# CH32X035F7P6-R0.net
KiCad netlist of a schematic drawn in Altium Designer
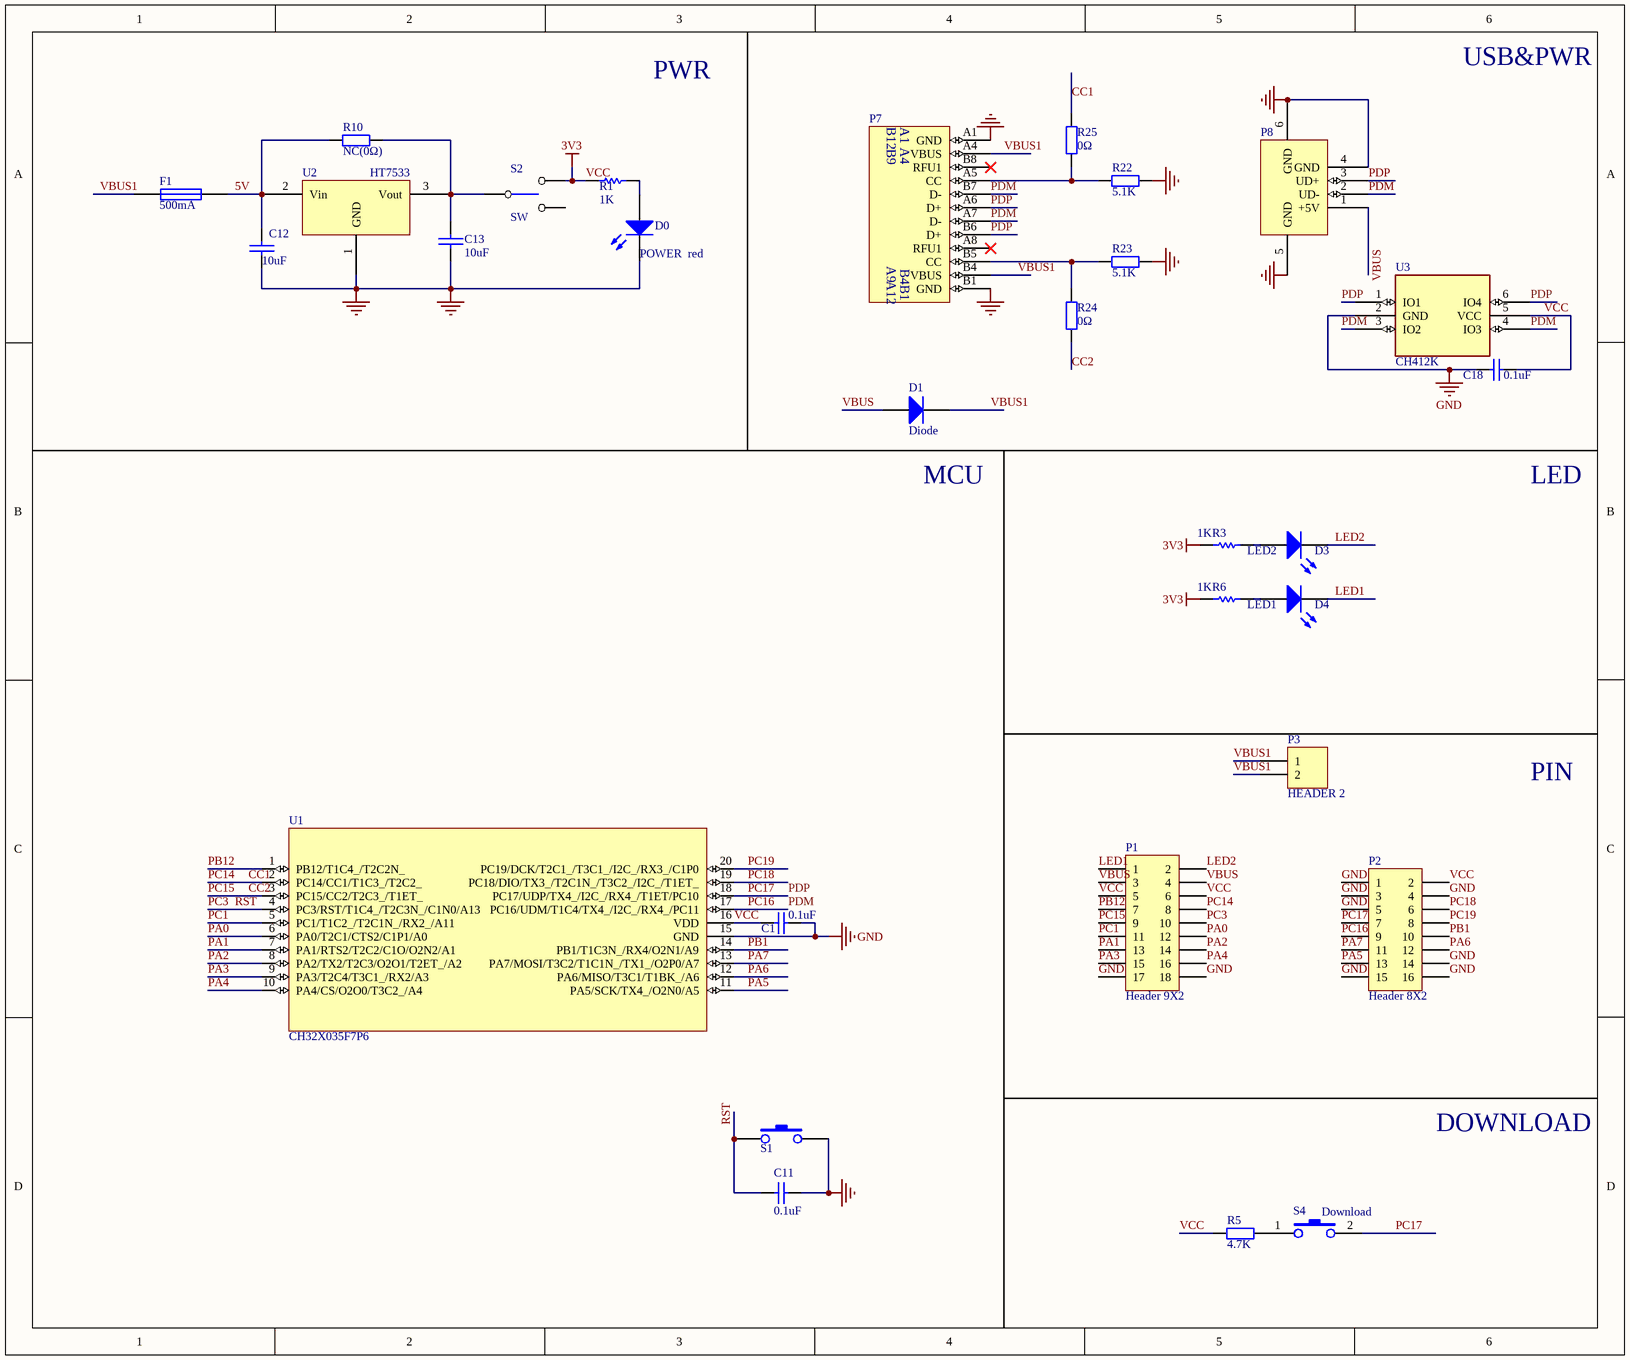
[diagram p0: CH32X035F7P6-R0.SchDoc]

(export (version "E")
  (design (tool "Eeschema 10.0.6"))
  (components
    (comp (ref "C1")
      (value "0.1uF")
      (footprint "0603_C")
      (description "Capacitor")
      (libsource (lib "Miscellaneous Devices") (part "Cap"))
    )
    (comp (ref "C11")
      (value "0.1uF")
      (footprint "0603_C")
      (description "Capacitor")
      (fields (field (name "PUBLISHER") "Altium Limited"))
      (libsource (lib "*") (part "Cap"))
    )
    (comp (ref "C12")
      (value "10uF")
      (footprint "0603_C")
      (description "Capacitor")
      (libsource (lib "*") (part "CAP"))
    )
    (comp (ref "C13")
      (value "10uF")
      (footprint "0603_C")
      (description "Capacitor")
      (libsource (lib "*") (part "CAP"))
    )
    (comp (ref "C18")
      (value "0.1uF")
      (footprint "0603_C")
      (description "Capacitor")
      (libsource (lib "Miscellaneous Devices") (part "Cap"))
    )
    (comp (ref "D0")
      (value "POWER  red")
      (footprint "0603+")
      (description "Typical INFRARED GaAs LED")
      (fields (field (name "PUBLISHER") "Altium Limited"))
      (libsource (lib "*") (part "LED0"))
    )
    (comp (ref "D1")
      (value "Diode")
      (footprint "SOD-123")
      (description "Default Diode")
      (fields (field (name "PUBLISHER") "Altium Limited"))
      (libsource (lib "Miscellaneous Devices") (part "Diode"))
    )
    (comp (ref "D3")
      (value "LED2")
      (footprint "0603+")
      (description "Typical INFRARED GaAs LED")
      (fields (field (name "PUBLISHER") "Altium Limited"))
      (libsource (lib "*") (part "LED0"))
    )
    (comp (ref "D4")
      (value "LED1")
      (footprint "0603+")
      (description "Typical INFRARED GaAs LED")
      (fields (field (name "PUBLISHER") "Altium Limited"))
      (libsource (lib "*") (part "LED0"))
    )
    (comp (ref "F1")
      (value "500mA")
      (footprint "0603")
      (description "Fuse")
      (libsource (lib "*") (part "FUSE1"))
    )
    (comp (ref "P1")
      (value "Header 9X2")
      (footprint "IDC18-2.54mm")
      (description "Header, 9-Pin, Dual row")
      (fields (field (name "PUBLISHER") "Altium Limited"))
      (libsource (lib "Miscellaneous Connectors") (part "Header 9X2"))
    )
    (comp (ref "P2")
      (value "Header 8X2")
      (footprint "IDC16-2.54mm")
      (description "Header, 8-Pin, Dual row")
      (fields (field (name "PUBLISHER") "Altium Limited"))
      (libsource (lib "Miscellaneous Connectors") (part "Header 8X2"))
    )
    (comp (ref "P3")
      (value "HEADER 2")
      (footprint "SIP2-2.54mm")
      (description "Header, 2-Pin")
      (libsource (lib "wch_sch_others") (part "HEADER 2"))
    )
    (comp (ref "P7")
      (value "TYPE-C")
      (footprint "TYPE-C-Receptacle-2.0")
      (libsource (lib "*") (part "TYPE-C1"))
    )
    (comp (ref "P8")
      (value "USB_A")
      (footprint "USBAF")
      (description "USB Port")
      (libsource (lib "*") (part "USB"))
    )
    (comp (ref "R1")
      (value "1K")
      (footprint "0603")
      (description "Semiconductor Resistor")
      (libsource (lib "*") (part "Res Semi"))
    )
    (comp (ref "R3")
      (value "1K")
      (footprint "0603")
      (description "Semiconductor Resistor")
      (libsource (lib "*") (part "Res Semi"))
    )
    (comp (ref "R5")
      (value "4.7K")
      (footprint "0603")
      (description "Resistor")
      (libsource (lib "") (part "Res2_1"))
    )
    (comp (ref "R6")
      (value "1K")
      (footprint "0603")
      (description "Semiconductor Resistor")
      (libsource (lib "*") (part "Res Semi"))
    )
    (comp (ref "R10")
      (value "NC(0Ω)")
      (footprint "0603")
      (description "Resistor")
      (libsource (lib "*") (part "Res2"))
    )
    (comp (ref "R22")
      (value "5.1K")
      (footprint "0603")
      (description "Resistor")
      (libsource (lib "") (part "Res2_1"))
    )
    (comp (ref "R23")
      (value "5.1K")
      (footprint "0603")
      (description "Resistor")
      (libsource (lib "") (part "Res2_1"))
    )
    (comp (ref "R24")
      (value "0Ω")
      (footprint "0603")
      (description "Resistor")
      (libsource (lib "Miscellaneous Devices") (part "Res2"))
    )
    (comp (ref "R25")
      (value "0Ω")
      (footprint "0603")
      (description "Resistor")
      (libsource (lib "Miscellaneous Devices") (part "Res2"))
    )
    (comp (ref "S1") (value "KEY") (footprint "贴片按键") (libsource (lib "*") (part "KEY")))
    (comp (ref "S2") (value "SW") (footprint "SW1") (libsource (lib "*") (part "SW")))
    (comp (ref "S4")
      (value "Download")
      (footprint "SMD_6.1x3.65x2.5mm-KEY")
      (libsource (lib "wch_sch_others") (part "KEY1"))
    )
    (comp (ref "U1")
      (value "CH32X035F7P6")
      (footprint "TSSOP20")
      (description "RISC-V MCU with USB/PD/ADC/SPI/I2C/UART/OA/CMP")
      (libsource (lib "DHXXXSCH") (part "CH32X035F7P6"))
    )
    (comp (ref "U2")
      (value "HT7533")
      (footprint "SOT-89")
      (libsource (lib "wch_sch_others") (part "1117-3.3V"))
    )
    (comp (ref "U3")
      (value "CH412K")
      (footprint "SOT-363")
      (description "Qaud ESD protect, high speed")
      (libsource (lib "CHXXX") (part "CH412K"))
    )
  )
  (nets
    (net (code "1") (name "/5V") (class "Default")
      (node (ref "C12") (pin "1") (pinfunction "1_1") (pintype "passive"))
      (node (ref "F1") (pin "2") (pinfunction "2_2") (pintype "passive"))
      (node (ref "R10") (pin "2") (pinfunction "2_2") (pintype "passive"))
      (node (ref "U2") (pin "2") (pinfunction "Vin_2") (pintype "passive"))
    )
    (net (code "3") (name "/CC1") (class "Default")
      (node (ref "P1") (pin "8") (pinfunction "8_8") (pintype "passive"))
      (node (ref "R25") (pin "2") (pinfunction "2_2") (pintype "passive"))
      (node (ref "U1") (pin "2") (pinfunction "PC14/CC1/T1C3_/T2C2__2") (pintype "bidirectional"))
    )
    (net (code "4") (name "/CC2") (class "Default")
      (node (ref "P1") (pin "9") (pinfunction "9_9") (pintype "passive"))
      (node (ref "R24") (pin "1") (pinfunction "1_1") (pintype "passive"))
      (node (ref "U1") (pin "3") (pinfunction "PC15/CC2/T2C3_/T1ET__3") (pintype "bidirectional"))
    )
    (net (code "5") (name "/LED1") (class "Default")
      (node (ref "D4") (pin "2") (pinfunction "K_2") (pintype "passive"))
      (node (ref "P1") (pin "1") (pinfunction "1_1") (pintype "passive"))
    )
    (net (code "6") (name "/LED2") (class "Default")
      (node (ref "D3") (pin "2") (pinfunction "K_2") (pintype "passive"))
      (node (ref "P1") (pin "2") (pinfunction "2_2") (pintype "passive"))
    )
    (net (code "7") (name "/PA0") (class "Default")
      (node (ref "P1") (pin "12") (pinfunction "12_12") (pintype "passive"))
      (node (ref "U1") (pin "6") (pinfunction "PA0/T2C1/CTS2/C1P1/A0_6") (pintype "bidirectional"))
    )
    (net (code "8") (name "/PA1") (class "Default")
      (node (ref "P1") (pin "13") (pinfunction "13_13") (pintype "passive"))
      (node (ref "U1") (pin "7") (pinfunction "PA1/RTS2/T2C2/C1O/O2N2/A1_7") (pintype "bidirectional"))
    )
    (net (code "9") (name "/PA2") (class "Default")
      (node (ref "P1") (pin "14") (pinfunction "14_14") (pintype "passive"))
      (node (ref "U1") (pin "8") (pinfunction "PA2/TX2/T2C3/O2O1/T2ET_/A2_8") (pintype "bidirectional"))
    )
    (net (code "10") (name "/PA3") (class "Default")
      (node (ref "P1") (pin "15") (pinfunction "15_15") (pintype "passive"))
      (node (ref "U1") (pin "9") (pinfunction "PA3/T2C4/T3C1_/RX2/A3_9") (pintype "bidirectional"))
    )
    (net (code "11") (name "/PA4") (class "Default")
      (node (ref "P1") (pin "16") (pinfunction "16_16") (pintype "passive"))
      (node (ref "U1") (pin "10") (pinfunction "PA4/CS/O2O0/T3C2_/A4_10") (pintype "bidirectional"))
    )
    (net (code "12") (name "/PA5") (class "Default")
      (node (ref "P2") (pin "13") (pinfunction "13_13") (pintype "passive"))
      (node (ref "U1") (pin "11") (pinfunction "PA5/SCK/TX4_/O2N0/A5_11") (pintype "bidirectional"))
    )
    (net (code "13") (name "/PA6") (class "Default")
      (node (ref "P2") (pin "12") (pinfunction "12_12") (pintype "passive"))
      (node (ref "U1") (pin "12") (pinfunction "PA6/MISO/T3C1/T1BK_/A6_12") (pintype "bidirectional"))
    )
    (net (code "14") (name "/PA7") (class "Default")
      (node (ref "P2") (pin "11") (pinfunction "11_11") (pintype "passive"))
      (node (ref "U1") (pin "13") (pinfunction "PA7/MOSI/T3C2/T1C1N_/TX1_/O2P0/A7_13") (pintype "bidirectional"))
    )
    (net (code "15") (name "/PB1") (class "Default")
      (node (ref "P2") (pin "10") (pinfunction "10_10") (pintype "passive"))
      (node (ref "U1") (pin "14") (pinfunction "PB1/T1C3N_/RX4/O2N1/A9_14") (pintype "bidirectional"))
    )
    (net (code "16") (name "/PB12") (class "Default")
      (node (ref "P1") (pin "7") (pinfunction "7_7") (pintype "passive"))
      (node (ref "U1") (pin "1") (pinfunction "PB12/T1C4_/T2C2N__1") (pintype "bidirectional"))
    )
    (net (code "17") (name "/PC1") (class "Default")
      (node (ref "P1") (pin "11") (pinfunction "11_11") (pintype "passive"))
      (node (ref "U1") (pin "5") (pinfunction "PC1/T1C2_/T2C1N_/RX2_/A11_5") (pintype "bidirectional"))
    )
    (net (code "18") (name "/PC3") (class "Default")
      (node (ref "C11") (pin "2") (pinfunction "2_2") (pintype "passive"))
      (node (ref "P1") (pin "10") (pinfunction "10_10") (pintype "passive"))
      (node (ref "S1") (pin "1") (pinfunction "1_1") (pintype "passive"))
      (node (ref "U1") (pin "4") (pinfunction "PC3/RST/T1C4_/T2C3N_/C1N0/A13_4") (pintype "bidirectional"))
    )
    (net (code "19") (name "/PC16") (class "Default")
      (node (ref "P2") (pin "9") (pinfunction "9_9") (pintype "passive"))
      (node (ref "P7") (pin "A7") (pinfunction "D-_A7") (pintype "bidirectional"))
      (node (ref "P7") (pin "B7") (pinfunction "D-_B7") (pintype "bidirectional"))
      (node (ref "P8") (pin "2") (pinfunction "UD-_2") (pintype "bidirectional"))
      (node (ref "U1") (pin "17") (pinfunction "PC16/UDM/T1C4/TX4_/I2C_/RX4_/PC11_17") (pintype "bidirectional"))
      (node (ref "U3") (pin "3") (pinfunction "IO2_3") (pintype "bidirectional"))
      (node (ref "U3") (pin "4") (pinfunction "IO3_4") (pintype "bidirectional"))
    )
    (net (code "20") (name "/PC17") (class "Default")
      (node (ref "P2") (pin "7") (pinfunction "7_7") (pintype "passive"))
      (node (ref "P7") (pin "A6") (pinfunction "D+_A6") (pintype "bidirectional"))
      (node (ref "P7") (pin "B6") (pinfunction "D+_B6") (pintype "bidirectional"))
      (node (ref "P8") (pin "3") (pinfunction "UD+_3") (pintype "bidirectional"))
      (node (ref "S4") (pin "2") (pinfunction "2_2") (pintype "passive"))
      (node (ref "U1") (pin "18") (pinfunction "PC17/UDP/TX4_/I2C_/RX4_/T1ET/PC10_18") (pintype "bidirectional"))
      (node (ref "U3") (pin "1") (pinfunction "IO1_1") (pintype "bidirectional"))
      (node (ref "U3") (pin "6") (pinfunction "IO4_6") (pintype "bidirectional"))
    )
    (net (code "21") (name "/PC18") (class "Default")
      (node (ref "P2") (pin "6") (pinfunction "6_6") (pintype "passive"))
      (node (ref "U1") (pin "19") (pinfunction "PC18/DIO/TX3_/T2C1N_/T3C2_/I2C_/T1ET__19") (pintype "bidirectional"))
    )
    (net (code "22") (name "/PC19") (class "Default")
      (node (ref "P2") (pin "8") (pinfunction "8_8") (pintype "passive"))
      (node (ref "U1") (pin "20") (pinfunction "PC19/DCK/T2C1_/T3C1_/I2C_/RX3_/C1P0_20") (pintype "bidirectional"))
    )
    (net (code "23") (name "/VBUS") (class "Default")
      (node (ref "D1") (pin "1") (pinfunction "A_1") (pintype "passive"))
      (node (ref "P1") (pin "3") (pinfunction "3_3") (pintype "passive"))
      (node (ref "P1") (pin "4") (pinfunction "4_4") (pintype "passive"))
      (node (ref "P8") (pin "1") (pinfunction "+5V_1") (pintype "power_in"))
    )
    (net (code "24") (name "/VBUS1") (class "Default")
      (node (ref "D1") (pin "2") (pinfunction "K_2") (pintype "passive"))
      (node (ref "F1") (pin "1") (pinfunction "1_1") (pintype "passive"))
      (node (ref "P3") (pin "1") (pinfunction "1_1") (pintype "passive"))
      (node (ref "P3") (pin "2") (pinfunction "2_2") (pintype "passive"))
      (node (ref "P7") (pin "A4") (pinfunction "VBUS_A4") (pintype "bidirectional"))
      (node (ref "P7") (pin "B4") (pinfunction "VBUS_B4") (pintype "bidirectional"))
    )
    (net (code "25") (name "3V3") (class "Default")
      (node (ref "C1") (pin "2") (pinfunction "2_2") (pintype "passive"))
      (node (ref "C18") (pin "2") (pinfunction "2_2") (pintype "passive"))
      (node (ref "P1") (pin "5") (pinfunction "5_5") (pintype "passive"))
      (node (ref "P1") (pin "6") (pinfunction "6_6") (pintype "passive"))
      (node (ref "P2") (pin "2") (pinfunction "2_2") (pintype "passive"))
      (node (ref "R1") (pin "2") (pinfunction "2_2") (pintype "passive"))
      (node (ref "R3") (pin "1") (pinfunction "1_1") (pintype "passive"))
      (node (ref "R5") (pin "1") (pinfunction "1_1") (pintype "passive"))
      (node (ref "R6") (pin "1") (pinfunction "1_1") (pintype "passive"))
      (node (ref "S2") (pin "3") (pinfunction "3_3") (pintype "passive"))
      (node (ref "U1") (pin "16") (pinfunction "VDD_16") (pintype "power_in"))
      (node (ref "U3") (pin "5") (pinfunction "VCC_5") (pintype "power_in"))
    )
    (net (code "26") (name "GND") (class "Default")
      (node (ref "C1") (pin "1") (pinfunction "1_1") (pintype "passive"))
      (node (ref "C11") (pin "1") (pinfunction "1_1") (pintype "passive"))
      (node (ref "C12") (pin "2") (pinfunction "2_2") (pintype "passive"))
      (node (ref "C13") (pin "2") (pinfunction "2_2") (pintype "passive"))
      (node (ref "C18") (pin "1") (pinfunction "1_1") (pintype "passive"))
      (node (ref "D0") (pin "2") (pinfunction "K_2") (pintype "passive"))
      (node (ref "P1") (pin "17") (pinfunction "17_17") (pintype "passive"))
      (node (ref "P1") (pin "18") (pinfunction "18_18") (pintype "passive"))
      (node (ref "P2") (pin "1") (pinfunction "1_1") (pintype "passive"))
      (node (ref "P2") (pin "14") (pinfunction "14_14") (pintype "passive"))
      (node (ref "P2") (pin "15") (pinfunction "15_15") (pintype "passive"))
      (node (ref "P2") (pin "16") (pinfunction "16_16") (pintype "passive"))
      (node (ref "P2") (pin "3") (pinfunction "3_3") (pintype "passive"))
      (node (ref "P2") (pin "4") (pinfunction "4_4") (pintype "passive"))
      (node (ref "P2") (pin "5") (pinfunction "5_5") (pintype "passive"))
      (node (ref "P7") (pin "A1") (pinfunction "GND_A1") (pintype "bidirectional"))
      (node (ref "P7") (pin "B1") (pinfunction "GND_B1") (pintype "bidirectional"))
      (node (ref "P8") (pin "4") (pinfunction "GND_4") (pintype "power_in"))
      (node (ref "P8") (pin "5") (pinfunction "GND_5") (pintype "power_in"))
      (node (ref "P8") (pin "6") (pinfunction "GND_6") (pintype "power_in"))
      (node (ref "R22") (pin "2") (pinfunction "2_2") (pintype "passive"))
      (node (ref "R23") (pin "2") (pinfunction "2_2") (pintype "passive"))
      (node (ref "S1") (pin "3") (pinfunction "3_3") (pintype "passive"))
      (node (ref "U1") (pin "15") (pinfunction "GND_15") (pintype "power_in"))
      (node (ref "U2") (pin "1") (pinfunction "GND_1") (pintype "passive"))
      (node (ref "U3") (pin "2") (pinfunction "GND_2") (pintype "power_in"))
    )
    (net (code "27") (name "Net-(D0-A)") (class "Default")
      (node (ref "D0") (pin "1") (pinfunction "A_1") (pintype "passive"))
      (node (ref "R1") (pin "1") (pinfunction "1_1") (pintype "passive"))
    )
    (net (code "28") (name "Net-(D3-A)") (class "Default")
      (node (ref "D3") (pin "1") (pinfunction "A_1") (pintype "passive"))
      (node (ref "R3") (pin "2") (pinfunction "2_2") (pintype "passive"))
    )
    (net (code "29") (name "Net-(D4-A)") (class "Default")
      (node (ref "D4") (pin "1") (pinfunction "A_1") (pintype "passive"))
      (node (ref "R6") (pin "2") (pinfunction "2_2") (pintype "passive"))
    )
    (net (code "30") (name "Net-(P7-CC-PadA5)") (class "Default")
      (node (ref "P7") (pin "A5") (pinfunction "CC_A5") (pintype "bidirectional"))
      (node (ref "R22") (pin "1") (pinfunction "1_1") (pintype "passive"))
      (node (ref "R25") (pin "1") (pinfunction "1_1") (pintype "passive"))
    )
    (net (code "31") (name "Net-(P7-CC-PadB5)") (class "Default")
      (node (ref "P7") (pin "B5") (pinfunction "CC_B5") (pintype "bidirectional"))
      (node (ref "R23") (pin "1") (pinfunction "1_1") (pintype "passive"))
      (node (ref "R24") (pin "2") (pinfunction "2_2") (pintype "passive"))
    )
    (net (code "32") (name "Net-(R5-Pad2)") (class "Default")
      (node (ref "R5") (pin "2") (pinfunction "2_2") (pintype "passive"))
      (node (ref "S4") (pin "1") (pinfunction "1_1") (pintype "passive"))
    )
    (net (code "33") (name "Net-(U2-Vout)") (class "Default")
      (node (ref "C13") (pin "1") (pinfunction "1_1") (pintype "passive"))
      (node (ref "R10") (pin "1") (pinfunction "1_1") (pintype "passive"))
      (node (ref "S2") (pin "1") (pinfunction "1_1") (pintype "passive"))
      (node (ref "U2") (pin "3") (pinfunction "Vout_3") (pintype "passive"))
    )
    (net (code "34") (name "unconnected-(P7-RFU1-PadA8)") (class "Default")
      (node (ref "P7") (pin "A8") (pinfunction "RFU1_A8") (pintype "bidirectional+no_connect"))
    )
    (net (code "35") (name "unconnected-(P7-RFU1-PadB8)") (class "Default")
      (node (ref "P7") (pin "B8") (pinfunction "RFU1_B8") (pintype "bidirectional+no_connect"))
    )
    (net (code "36") (name "unconnected-(S2-Pad2)") (class "Default")
      (node (ref "S2") (pin "2") (pinfunction "2_2") (pintype "passive"))
    )
  )
)
